# IR.net
KiCad netlist of a schematic drawn in Altium Designer
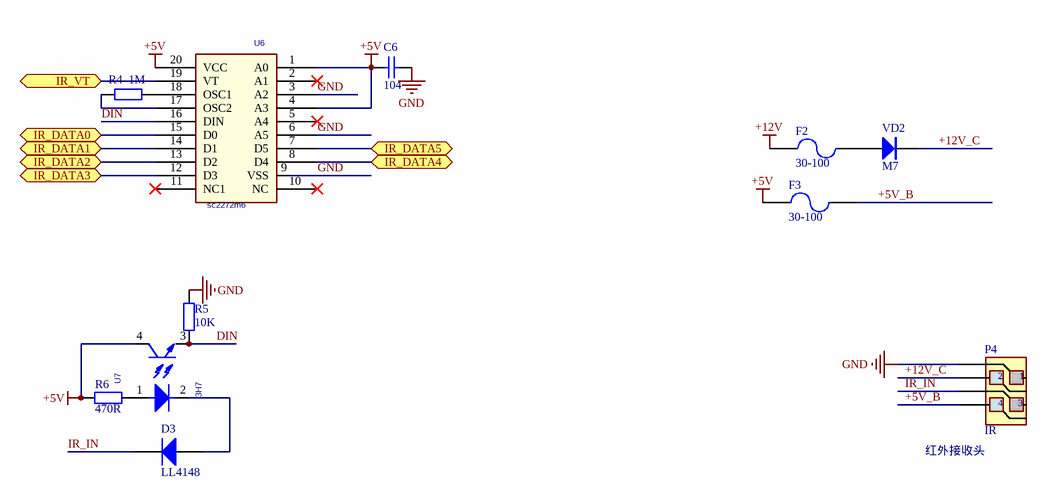
[diagram p0: IR.SchDoc]

(export (version "E")
  (design (tool "Eeschema 10.0.6"))
  (components
    (comp (ref "C6")
      (value "104")
      (footprint "C 0805")
      (libsource (lib "YXF_ComponentLibrary") (part "Cap1"))
    )
    (comp (ref "D3") (value "LL4148") (footprint "MINI_MELF (LL34)") (libsource (lib "any") (part "Diode")))
    (comp (ref "F2")
      (value "30-100")
      (footprint "FU 1812")
      (description "Fuse")
      (fields (field (name "PUBLISHER") "Altium Limited"))
      (libsource (lib "YXF_ComponentLibrary") (part "Fuse 2"))
    )
    (comp (ref "F3")
      (value "30-100")
      (footprint "FU 1812")
      (description "Fuse")
      (fields (field (name "PUBLISHER") "Altium Limited"))
      (libsource (lib "YXF_ComponentLibrary") (part "Fuse 2"))
    )
    (comp (ref "P4")
      (value "IR")
      (footprint "557-2x2")
      (description "接插件")
      (libsource (lib "YXF_ComponentLibrary") (part "557-2x2"))
    )
    (comp (ref "R4")
      (value "1M")
      (footprint "R 0805")
      (description "Resistor")
      (fields (field (name "PUBLISHER") "Altium Limited"))
      (libsource (lib "Miscellaneous Devices") (part "Res2"))
    )
    (comp (ref "R5") (value "10K") (footprint "R 0805") (libsource (lib "") (part "Res1_1")))
    (comp (ref "R6") (value "470R") (footprint "R 0805") (libsource (lib "any") (part "Res1")))
    (comp (ref "U6") (value "sc2272m6") (footprint "SOP20_N") (libsource (lib "*") (part "PT2272_L6S")))
    (comp (ref "U7") (value "3H7") (libsource (lib "*") (part "PS2801-1/SM")))
    (comp (ref "VD2")
      (value "M7")
      (footprint "SMA")
      (description "整流二极管")
      (fields (field (name "版权归属") "源创客"))
      (libsource (lib "二极管-整流桥") (part "M7"))
    )
  )
  (nets
    (net (code "1") (name "+5V") (class "Default")
      (node (ref "C6") (pin "2") (pinfunction "2_2") (pintype "passive"))
      (node (ref "F3") (pin "1") (pinfunction "1_1") (pintype "passive"))
      (node (ref "R6") (pin "2") (pinfunction "2_2") (pintype "passive"))
      (node (ref "U6") (pin "1") (pinfunction "A0_1") (pintype "passive"))
      (node (ref "U6") (pin "20") (pinfunction "VCC_20") (pintype "passive"))
      (node (ref "U6") (pin "4") (pinfunction "A3_4") (pintype "passive"))
      (node (ref "U7") (pin "4") (pinfunction "COLLECTOR_4") (pintype "passive"))
    )
    (net (code "2") (name "+12V") (class "Default")
      (node (ref "F2") (pin "1") (pinfunction "1_1") (pintype "passive"))
    )
    (net (code "3") (name "/+5V_B") (class "Default")
      (node (ref "F3") (pin "2") (pinfunction "2_2") (pintype "passive"))
      (node (ref "P4") (pin "4") (pinfunction "4_4") (pintype "passive"))
    )
    (net (code "4") (name "/+12V_C") (class "Default")
      (node (ref "P4") (pin "2") (pinfunction "2_2") (pintype "passive"))
      (node (ref "VD2") (pin "2") (pinfunction "K_2") (pintype "passive"))
    )
    (net (code "5") (name "/DIN") (class "Default")
      (node (ref "R5") (pin "1") (pinfunction "1_1") (pintype "passive"))
      (node (ref "U6") (pin "16") (pinfunction "DIN_16") (pintype "passive"))
      (node (ref "U7") (pin "3") (pinfunction "EMITTER_3") (pintype "passive"))
    )
    (net (code "6") (name "/IR_DATA0") (class "Default")
      (node (ref "U6") (pin "15") (pinfunction "D0_15") (pintype "passive"))
    )
    (net (code "7") (name "/IR_DATA1") (class "Default")
      (node (ref "U6") (pin "14") (pinfunction "D1_14") (pintype "passive"))
    )
    (net (code "8") (name "/IR_DATA2") (class "Default")
      (node (ref "U6") (pin "13") (pinfunction "D2_13") (pintype "passive"))
    )
    (net (code "9") (name "/IR_DATA3") (class "Default")
      (node (ref "U6") (pin "12") (pinfunction "D3_12") (pintype "passive"))
    )
    (net (code "10") (name "/IR_DATA4") (class "Default")
      (node (ref "U6") (pin "8") (pinfunction "D4_8") (pintype "passive"))
    )
    (net (code "11") (name "/IR_DATA5") (class "Default")
      (node (ref "U6") (pin "7") (pinfunction "D5_7") (pintype "passive"))
    )
    (net (code "12") (name "/IR_IN") (class "Default")
      (node (ref "D3") (pin "2") (pinfunction "2_2") (pintype "passive"))
      (node (ref "P4") (pin "3") (pinfunction "3_3") (pintype "passive"))
    )
    (net (code "13") (name "/IR_VT") (class "Default")
      (node (ref "U6") (pin "19") (pinfunction "VT_19") (pintype "passive"))
    )
    (net (code "14") (name "GND") (class "Default")
      (node (ref "C6") (pin "1") (pinfunction "1_1") (pintype "passive"))
      (node (ref "P4") (pin "1") (pinfunction "1_1") (pintype "passive"))
      (node (ref "R5") (pin "2") (pinfunction "2_2") (pintype "passive"))
      (node (ref "U6") (pin "3") (pinfunction "A2_3") (pintype "passive"))
      (node (ref "U6") (pin "6") (pinfunction "A5_6") (pintype "passive"))
      (node (ref "U6") (pin "9") (pinfunction "VSS_9") (pintype "power_in"))
    )
    (net (code "15") (name "Net-(U6-OSC1)") (class "Default")
      (node (ref "R4") (pin "2") (pinfunction "2_2") (pintype "passive"))
      (node (ref "U6") (pin "18") (pinfunction "OSC1_18") (pintype "passive"))
    )
    (net (code "16") (name "Net-(U6-OSC2)") (class "Default")
      (node (ref "R4") (pin "1") (pinfunction "1_1") (pintype "passive"))
      (node (ref "U6") (pin "17") (pinfunction "OSC2_17") (pintype "passive"))
    )
    (net (code "17") (name "Net-(U7-ANODE)") (class "Default")
      (node (ref "R6") (pin "1") (pinfunction "1_1") (pintype "passive"))
      (node (ref "U7") (pin "1") (pinfunction "ANODE_1") (pintype "passive"))
    )
    (net (code "18") (name "Net-(U7-CATHODE)") (class "Default")
      (node (ref "D3") (pin "1") (pinfunction "1_1") (pintype "passive"))
      (node (ref "U7") (pin "2") (pinfunction "CATHODE_2") (pintype "passive"))
    )
    (net (code "19") (name "Net-(VD2-A)") (class "Default")
      (node (ref "F2") (pin "2") (pinfunction "2_2") (pintype "passive"))
      (node (ref "VD2") (pin "1") (pinfunction "A_1") (pintype "passive"))
    )
    (net (code "20") (name "unconnected-(U6-A1-Pad2)") (class "Default")
      (node (ref "U6") (pin "2") (pinfunction "A1_2") (pintype "passive+no_connect"))
    )
    (net (code "21") (name "unconnected-(U6-A4-Pad5)") (class "Default")
      (node (ref "U6") (pin "5") (pinfunction "A4_5") (pintype "passive+no_connect"))
    )
    (net (code "22") (name "unconnected-(U6-NC-Pad10)") (class "Default")
      (node (ref "U6") (pin "10") (pinfunction "NC_10") (pintype "passive+no_connect"))
    )
    (net (code "23") (name "unconnected-(U6-NC1-Pad11)") (class "Default")
      (node (ref "U6") (pin "11") (pinfunction "NC1_11") (pintype "passive+no_connect"))
    )
  )
)
